# LePacific.net
KiCad netlist of a schematic drawn in EAGLE
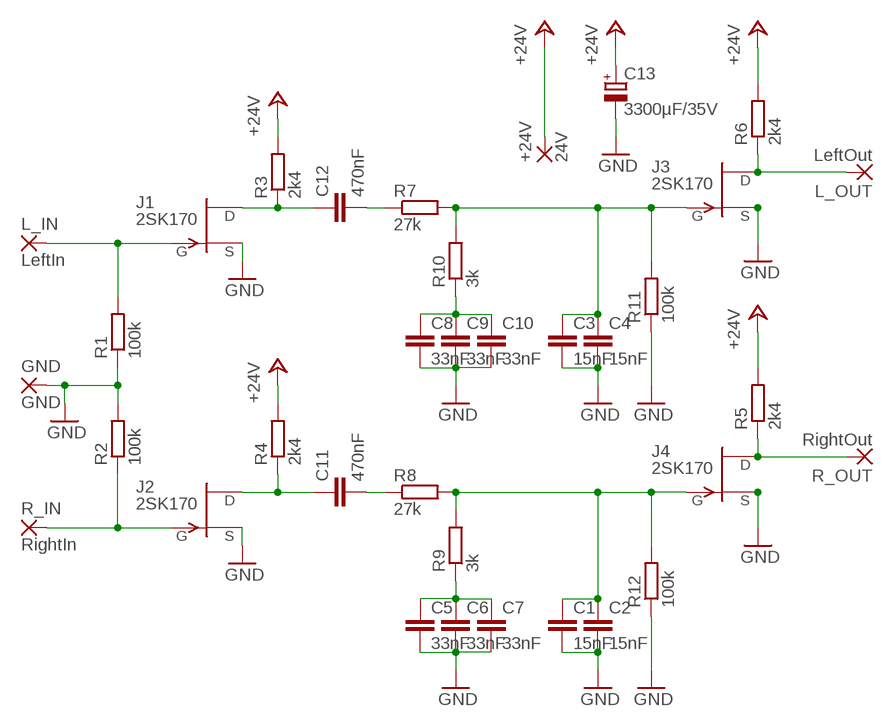
[diagram p0: schematic, sheet 1]

(export (version "E")
  (design (tool "Eeschema 10.0.6"))
  (components
    (comp (ref "+24V")
      (value "24V")
      (footprint "eagle-import:2,54_0,8")
      (libsource (lib "eagle-import") (part "2,54/0,8"))
    )
    (comp (ref "C1")
      (value "15nF")
      (footprint "eagle-import:C150-054X183")
      (libsource (lib "eagle-import") (part "C-EU150-054X183"))
    )
    (comp (ref "C2")
      (value "15nF")
      (footprint "eagle-import:C150-054X183")
      (libsource (lib "eagle-import") (part "C-EU150-054X183"))
    )
    (comp (ref "C3")
      (value "15nF")
      (footprint "eagle-import:C150-054X183")
      (libsource (lib "eagle-import") (part "C-EU150-054X183"))
    )
    (comp (ref "C4")
      (value "15nF")
      (footprint "eagle-import:C150-054X183")
      (libsource (lib "eagle-import") (part "C-EU150-054X183"))
    )
    (comp (ref "C5")
      (value "33nF")
      (footprint "eagle-import:C225-062X268")
      (libsource (lib "eagle-import") (part "C-EU225-062X268"))
    )
    (comp (ref "C6")
      (value "33nF")
      (footprint "eagle-import:C225-062X268")
      (libsource (lib "eagle-import") (part "C-EU225-062X268"))
    )
    (comp (ref "C7")
      (value "33nF")
      (footprint "eagle-import:C225-062X268")
      (libsource (lib "eagle-import") (part "C-EU225-062X268"))
    )
    (comp (ref "C8")
      (value "33nF")
      (footprint "eagle-import:C225-062X268")
      (libsource (lib "eagle-import") (part "C-EU225-062X268"))
    )
    (comp (ref "C9")
      (value "33nF")
      (footprint "eagle-import:C225-062X268")
      (libsource (lib "eagle-import") (part "C-EU225-062X268"))
    )
    (comp (ref "C10")
      (value "33nF")
      (footprint "eagle-import:C225-062X268")
      (libsource (lib "eagle-import") (part "C-EU225-062X268"))
    )
    (comp (ref "C11")
      (value "470nF")
      (footprint "eagle-import:C225-108X268")
      (libsource (lib "eagle-import") (part "C-EU225-108X268"))
    )
    (comp (ref "C12")
      (value "470nF")
      (footprint "eagle-import:C225-108X268")
      (libsource (lib "eagle-import") (part "C-EU225-108X268"))
    )
    (comp (ref "C13")
      (value "3300µF/35V")
      (footprint "eagle-import:E7,5-16")
      (libsource (lib "eagle-import") (part "CPOL-EUE7.5-16"))
    )
    (comp (ref "GND")
      (value "GND")
      (footprint "eagle-import:2,54_0,8")
      (libsource (lib "eagle-import") (part "2,54/0,8"))
    )
    (comp (ref "J1")
      (value "2SK170")
      (footprint "eagle-import:TO-92")
      (libsource (lib "eagle-import") (part "2SK170"))
    )
    (comp (ref "J2")
      (value "2SK170")
      (footprint "eagle-import:TO-92")
      (libsource (lib "eagle-import") (part "2SK170"))
    )
    (comp (ref "J3")
      (value "2SK170")
      (footprint "eagle-import:TO-92")
      (libsource (lib "eagle-import") (part "2SK170"))
    )
    (comp (ref "J4")
      (value "2SK170")
      (footprint "eagle-import:TO-92")
      (libsource (lib "eagle-import") (part "2SK170"))
    )
    (comp (ref "L_IN")
      (value "LeftIn")
      (footprint "eagle-import:2,54_0,8")
      (libsource (lib "eagle-import") (part "2,54/0,8"))
    )
    (comp (ref "L_OUT")
      (value "LeftOut")
      (footprint "eagle-import:2,54_0,8")
      (libsource (lib "eagle-import") (part "2,54/0,8"))
    )
    (comp (ref "R1")
      (value "100k")
      (footprint "eagle-import:0207_10")
      (libsource (lib "eagle-import") (part "R-EU_0207/10"))
    )
    (comp (ref "R2")
      (value "100k")
      (footprint "eagle-import:0207_10")
      (libsource (lib "eagle-import") (part "R-EU_0207/10"))
    )
    (comp (ref "R3")
      (value "2k4")
      (footprint "eagle-import:0207_10")
      (libsource (lib "eagle-import") (part "R-EU_0207/10"))
    )
    (comp (ref "R4")
      (value "2k4")
      (footprint "eagle-import:0207_10")
      (libsource (lib "eagle-import") (part "R-EU_0207/10"))
    )
    (comp (ref "R5")
      (value "2k4")
      (footprint "eagle-import:0207_10")
      (libsource (lib "eagle-import") (part "R-EU_0207/10"))
    )
    (comp (ref "R6")
      (value "2k4")
      (footprint "eagle-import:0207_10")
      (libsource (lib "eagle-import") (part "R-EU_0207/10"))
    )
    (comp (ref "R7")
      (value "27k")
      (footprint "eagle-import:0207_10")
      (libsource (lib "eagle-import") (part "R-EU_0207/10"))
    )
    (comp (ref "R8")
      (value "27k")
      (footprint "eagle-import:0207_10")
      (libsource (lib "eagle-import") (part "R-EU_0207/10"))
    )
    (comp (ref "R9")
      (value "3k")
      (footprint "eagle-import:0207_10")
      (libsource (lib "eagle-import") (part "R-EU_0207/10"))
    )
    (comp (ref "R10")
      (value "3k")
      (footprint "eagle-import:0207_10")
      (libsource (lib "eagle-import") (part "R-EU_0207/10"))
    )
    (comp (ref "R11")
      (value "100k")
      (footprint "eagle-import:0207_10")
      (libsource (lib "eagle-import") (part "R-EU_0207/10"))
    )
    (comp (ref "R12")
      (value "100k")
      (footprint "eagle-import:0207_10")
      (libsource (lib "eagle-import") (part "R-EU_0207/10"))
    )
    (comp (ref "R_IN")
      (value "RightIn")
      (footprint "eagle-import:2,54_0,8")
      (libsource (lib "eagle-import") (part "2,54/0,8"))
    )
    (comp (ref "R_OUT")
      (value "RightOut")
      (footprint "eagle-import:2,54_0,8")
      (libsource (lib "eagle-import") (part "2,54/0,8"))
    )
  )
  (nets
    (net (code "1") (name "+24V") (class "Default")
      (node (ref "+24V") (pin "1") (pinfunction "P_1") (pintype "passive"))
      (node (ref "C13") (pin "+") (pinfunction "+_+") (pintype "passive"))
      (node (ref "R3") (pin "2") (pinfunction "2_2") (pintype "passive"))
      (node (ref "R4") (pin "2") (pinfunction "2_2") (pintype "passive"))
      (node (ref "R5") (pin "2") (pinfunction "2_2") (pintype "passive"))
      (node (ref "R6") (pin "2") (pinfunction "2_2") (pintype "passive"))
    )
    (net (code "2") (name "GND") (class "Default")
      (node (ref "C1") (pin "2") (pinfunction "2_2") (pintype "passive"))
      (node (ref "C10") (pin "2") (pinfunction "2_2") (pintype "passive"))
      (node (ref "C13") (pin "-") (pinfunction "-_-") (pintype "passive"))
      (node (ref "C2") (pin "2") (pinfunction "2_2") (pintype "passive"))
      (node (ref "C3") (pin "2") (pinfunction "2_2") (pintype "passive"))
      (node (ref "C4") (pin "2") (pinfunction "2_2") (pintype "passive"))
      (node (ref "C5") (pin "2") (pinfunction "2_2") (pintype "passive"))
      (node (ref "C6") (pin "2") (pinfunction "2_2") (pintype "passive"))
      (node (ref "C7") (pin "2") (pinfunction "2_2") (pintype "passive"))
      (node (ref "C8") (pin "2") (pinfunction "2_2") (pintype "passive"))
      (node (ref "C9") (pin "2") (pinfunction "2_2") (pintype "passive"))
      (node (ref "GND") (pin "1") (pinfunction "P_1") (pintype "passive"))
      (node (ref "J1") (pin "3") (pinfunction "S_3") (pintype "passive"))
      (node (ref "J2") (pin "3") (pinfunction "S_3") (pintype "passive"))
      (node (ref "J3") (pin "3") (pinfunction "S_3") (pintype "passive"))
      (node (ref "J4") (pin "3") (pinfunction "S_3") (pintype "passive"))
      (node (ref "R1") (pin "1") (pinfunction "1_1") (pintype "passive"))
      (node (ref "R11") (pin "1") (pinfunction "1_1") (pintype "passive"))
      (node (ref "R12") (pin "1") (pinfunction "1_1") (pintype "passive"))
      (node (ref "R2") (pin "2") (pinfunction "2_2") (pintype "passive"))
    )
    (net (code "3") (name "Net-(C5-Pad1)") (class "Default")
      (node (ref "C5") (pin "1") (pinfunction "1_1") (pintype "passive"))
      (node (ref "C6") (pin "1") (pinfunction "1_1") (pintype "passive"))
      (node (ref "C7") (pin "1") (pinfunction "1_1") (pintype "passive"))
      (node (ref "R9") (pin "1") (pinfunction "1_1") (pintype "passive"))
    )
    (net (code "4") (name "Net-(C10-Pad1)") (class "Default")
      (node (ref "C10") (pin "1") (pinfunction "1_1") (pintype "passive"))
      (node (ref "C8") (pin "1") (pinfunction "1_1") (pintype "passive"))
      (node (ref "C9") (pin "1") (pinfunction "1_1") (pintype "passive"))
      (node (ref "R10") (pin "1") (pinfunction "1_1") (pintype "passive"))
    )
    (net (code "5") (name "Net-(C11-Pad2)") (class "Default")
      (node (ref "C11") (pin "2") (pinfunction "2_2") (pintype "passive"))
      (node (ref "R8") (pin "1") (pinfunction "1_1") (pintype "passive"))
    )
    (net (code "6") (name "Net-(C12-Pad2)") (class "Default")
      (node (ref "C12") (pin "2") (pinfunction "2_2") (pintype "passive"))
      (node (ref "R7") (pin "1") (pinfunction "1_1") (pintype "passive"))
    )
    (net (code "7") (name "Net-(J1-D)") (class "Default")
      (node (ref "C12") (pin "1") (pinfunction "1_1") (pintype "passive"))
      (node (ref "J1") (pin "1") (pinfunction "D_1") (pintype "passive"))
      (node (ref "R3") (pin "1") (pinfunction "1_1") (pintype "passive"))
    )
    (net (code "8") (name "Net-(J1-G)") (class "Default")
      (node (ref "J1") (pin "2") (pinfunction "G_2") (pintype "passive"))
      (node (ref "L_IN") (pin "1") (pinfunction "P_1") (pintype "passive"))
      (node (ref "R1") (pin "2") (pinfunction "2_2") (pintype "passive"))
    )
    (net (code "9") (name "Net-(J2-D)") (class "Default")
      (node (ref "C11") (pin "1") (pinfunction "1_1") (pintype "passive"))
      (node (ref "J2") (pin "1") (pinfunction "D_1") (pintype "passive"))
      (node (ref "R4") (pin "1") (pinfunction "1_1") (pintype "passive"))
    )
    (net (code "10") (name "Net-(J2-G)") (class "Default")
      (node (ref "J2") (pin "2") (pinfunction "G_2") (pintype "passive"))
      (node (ref "R2") (pin "1") (pinfunction "1_1") (pintype "passive"))
      (node (ref "R_IN") (pin "1") (pinfunction "P_1") (pintype "passive"))
    )
    (net (code "11") (name "Net-(J3-D)") (class "Default")
      (node (ref "J3") (pin "1") (pinfunction "D_1") (pintype "passive"))
      (node (ref "L_OUT") (pin "1") (pinfunction "P_1") (pintype "passive"))
      (node (ref "R6") (pin "1") (pinfunction "1_1") (pintype "passive"))
    )
    (net (code "12") (name "Net-(J3-G)") (class "Default")
      (node (ref "C3") (pin "1") (pinfunction "1_1") (pintype "passive"))
      (node (ref "C4") (pin "1") (pinfunction "1_1") (pintype "passive"))
      (node (ref "J3") (pin "2") (pinfunction "G_2") (pintype "passive"))
      (node (ref "R10") (pin "2") (pinfunction "2_2") (pintype "passive"))
      (node (ref "R11") (pin "2") (pinfunction "2_2") (pintype "passive"))
      (node (ref "R7") (pin "2") (pinfunction "2_2") (pintype "passive"))
    )
    (net (code "13") (name "Net-(J4-D)") (class "Default")
      (node (ref "J4") (pin "1") (pinfunction "D_1") (pintype "passive"))
      (node (ref "R5") (pin "1") (pinfunction "1_1") (pintype "passive"))
      (node (ref "R_OUT") (pin "1") (pinfunction "P_1") (pintype "passive"))
    )
    (net (code "14") (name "Net-(J4-G)") (class "Default")
      (node (ref "C1") (pin "1") (pinfunction "1_1") (pintype "passive"))
      (node (ref "C2") (pin "1") (pinfunction "1_1") (pintype "passive"))
      (node (ref "J4") (pin "2") (pinfunction "G_2") (pintype "passive"))
      (node (ref "R12") (pin "2") (pinfunction "2_2") (pintype "passive"))
      (node (ref "R8") (pin "2") (pinfunction "2_2") (pintype "passive"))
      (node (ref "R9") (pin "2") (pinfunction "2_2") (pintype "passive"))
    )
  )
)
